# display.net
KiCad netlist of a schematic drawn in EAGLE
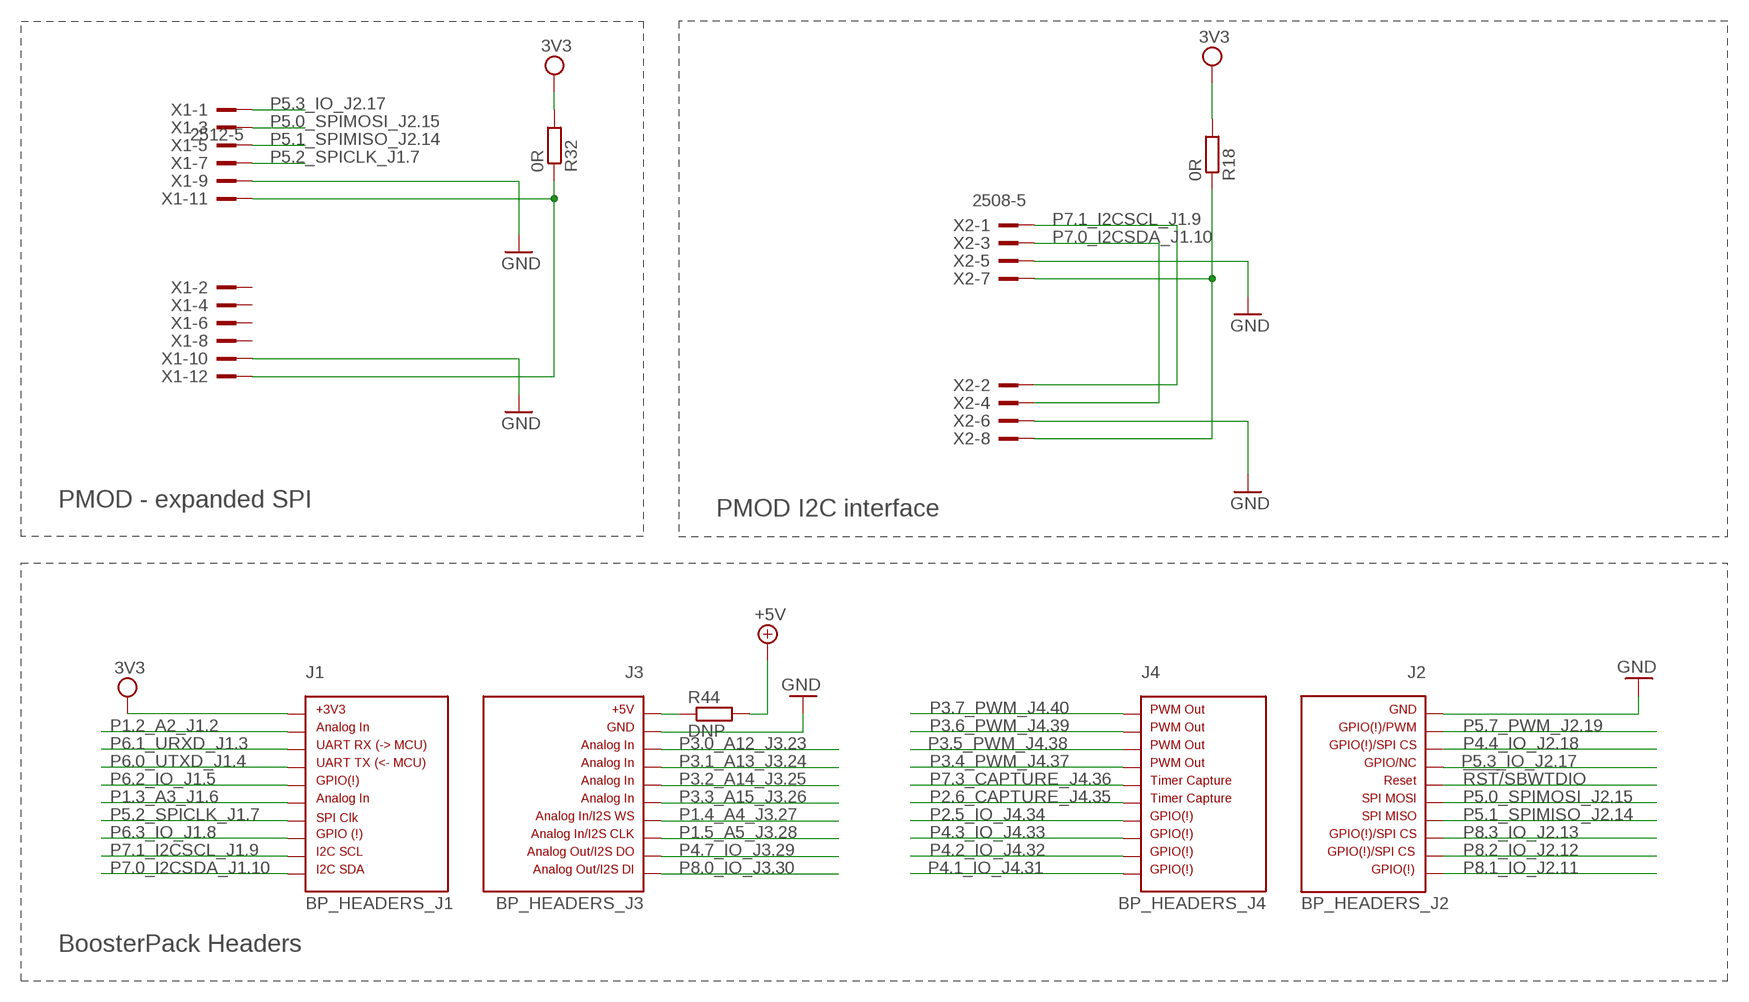
[diagram p0: schematic, sheet 1]
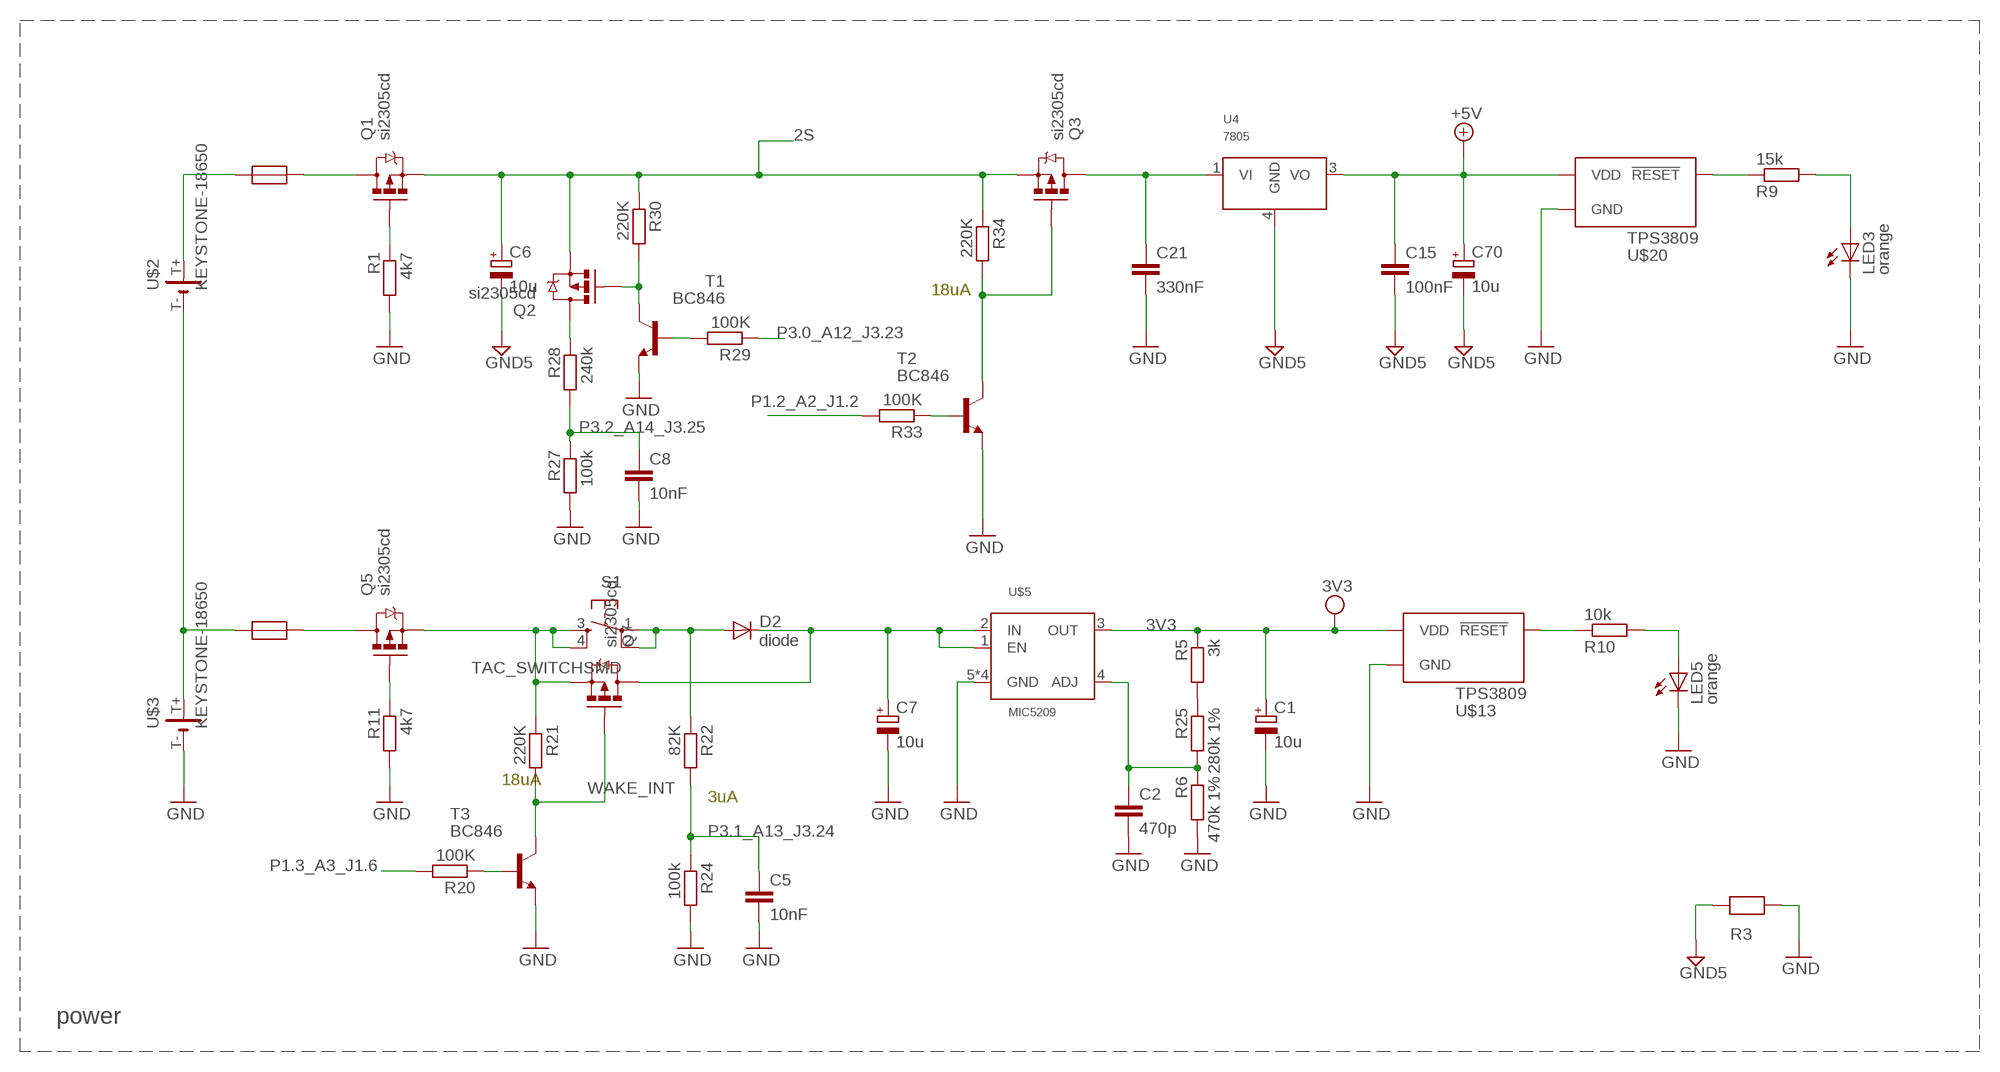
[diagram p1: schematic, sheet 2]
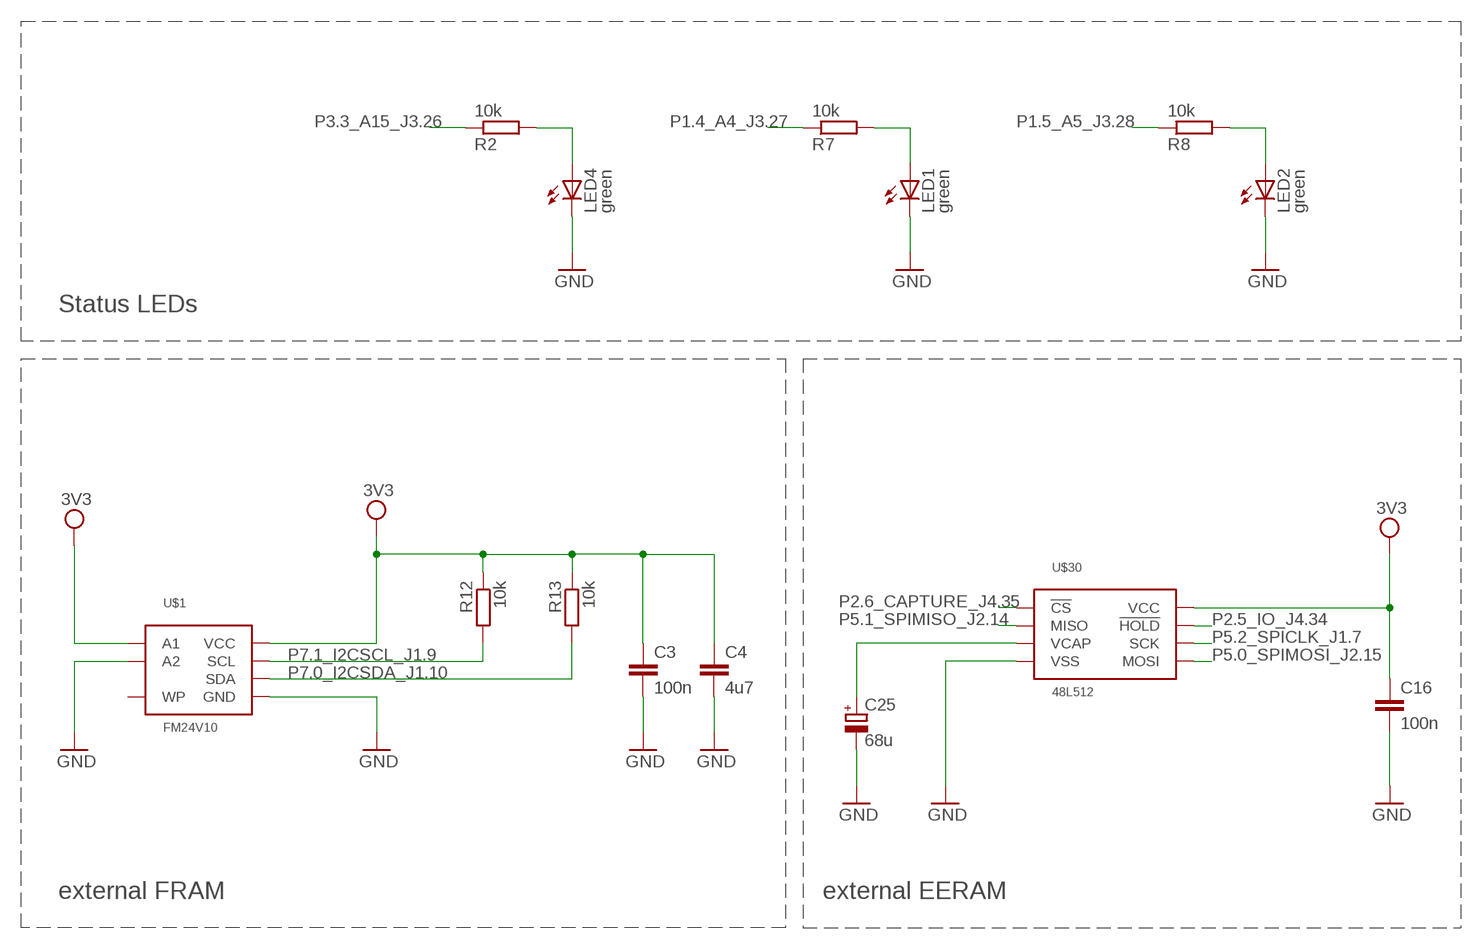
[diagram p2: schematic, sheet 3]
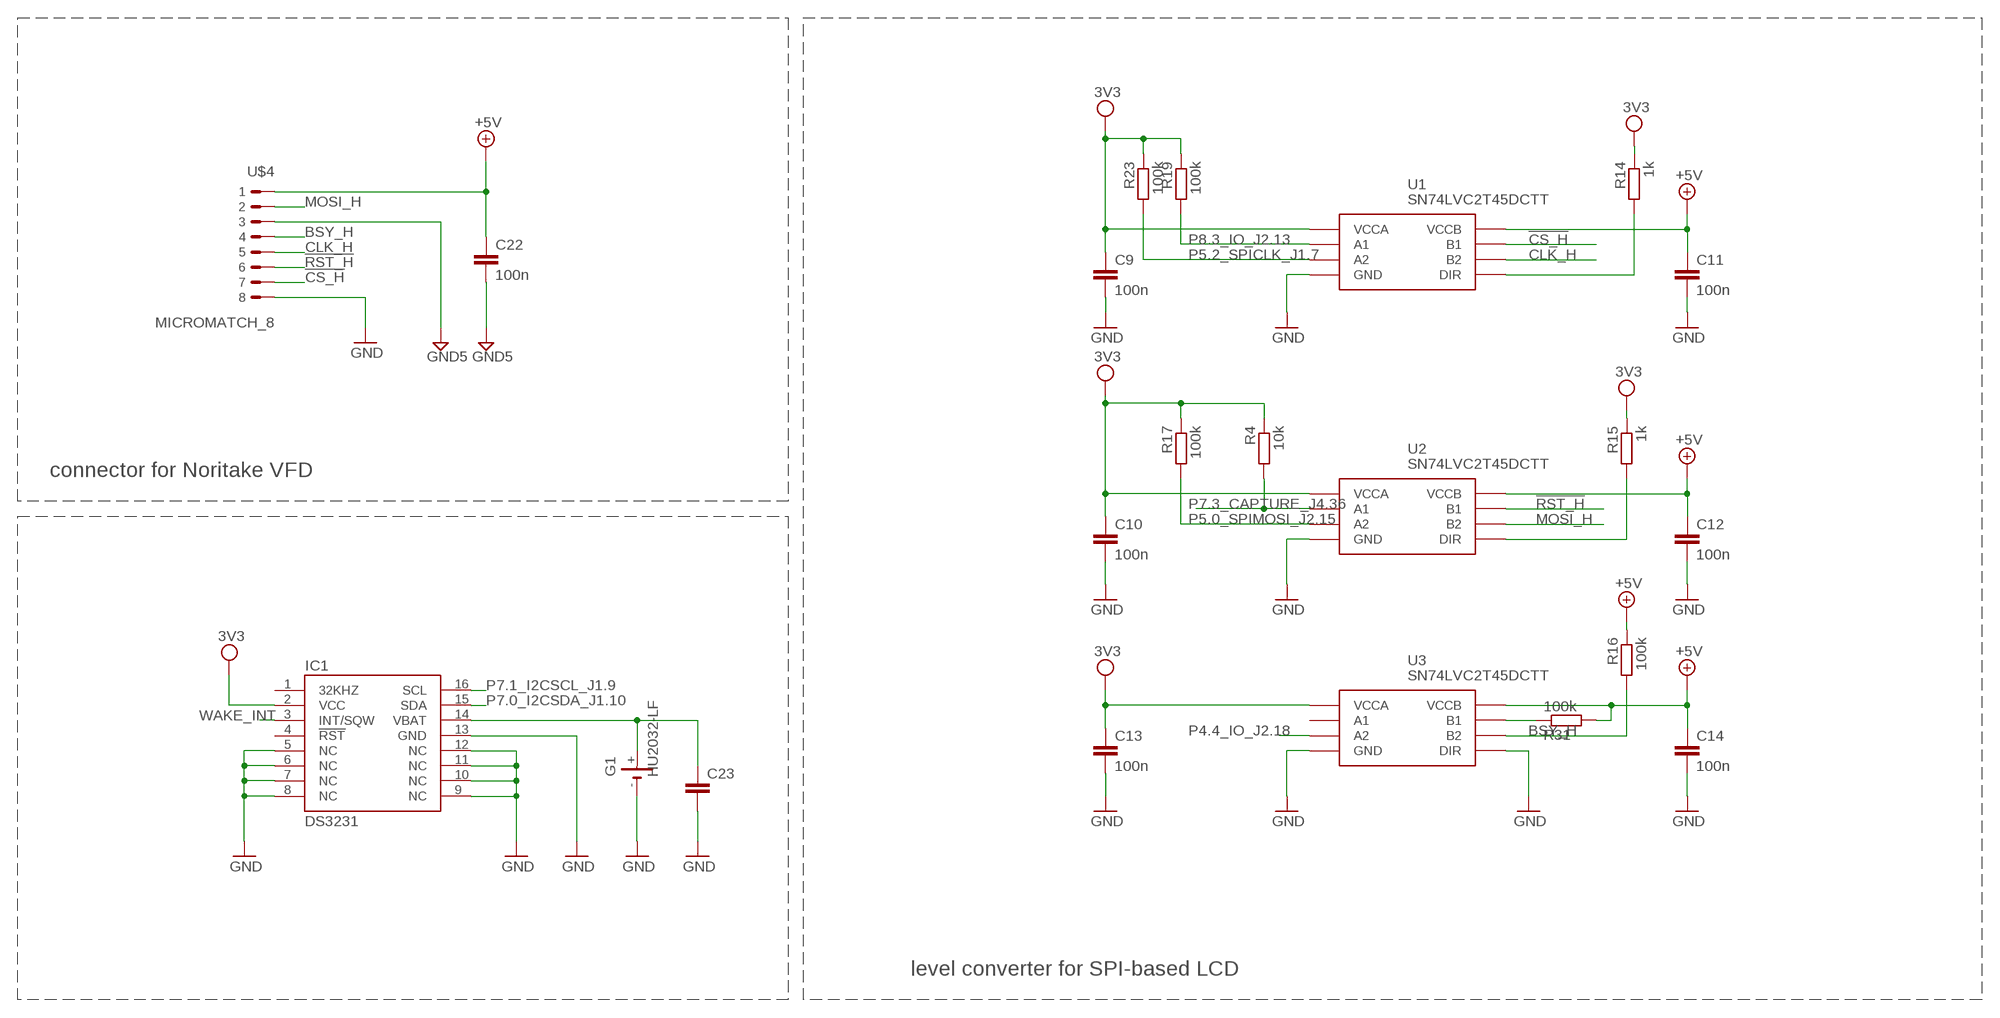
[diagram p3: schematic, sheet 4]
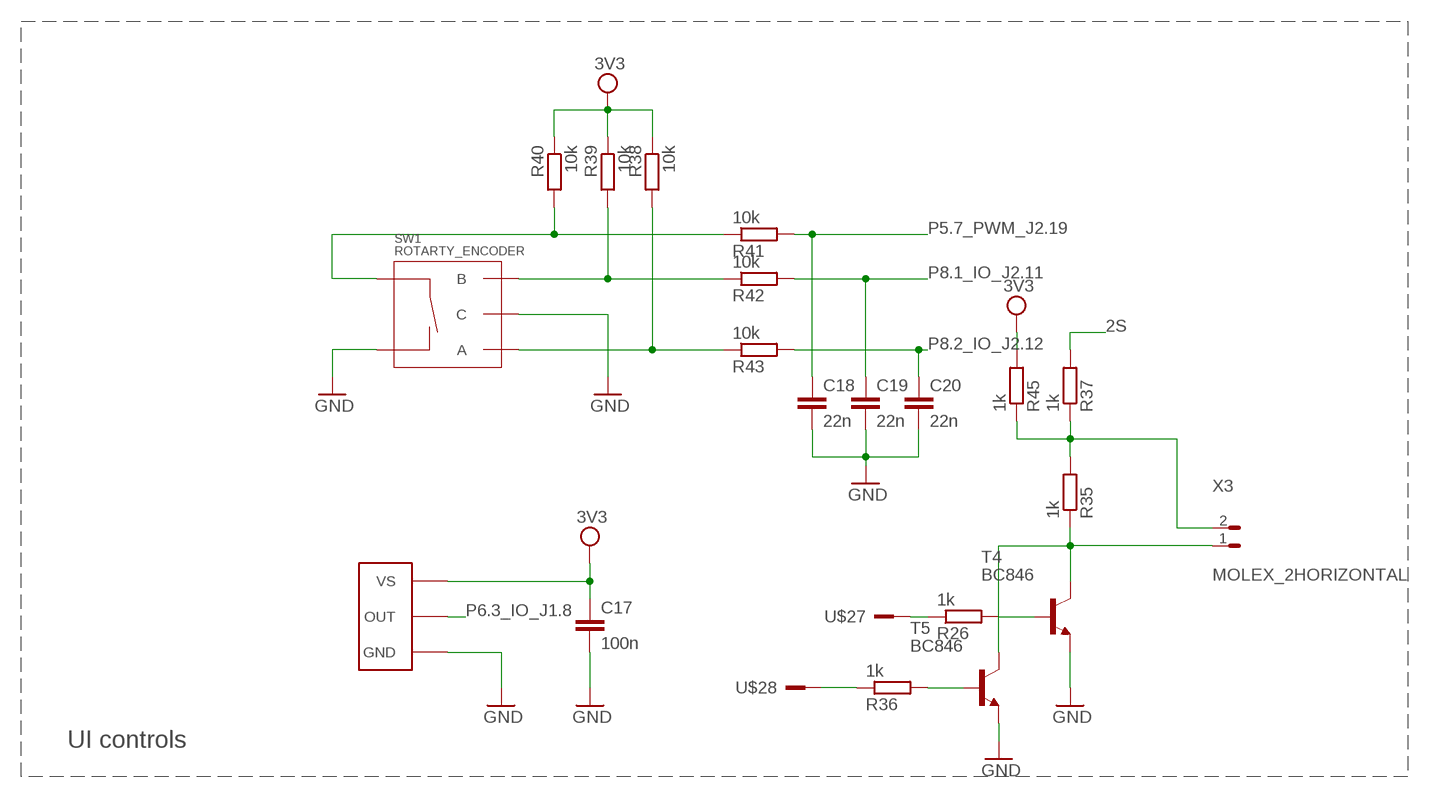
[diagram p4: schematic, sheet 5]

(export (version "E")
  (design (tool "Eeschema 10.0.6"))
  (components
    (comp (ref "C9")
      (value "100n")
      (footprint "eagle-import:C0805")
      (libsource (lib "eagle-import") (part "C-EUC0805"))
    )
    (comp (ref "C10")
      (value "100n")
      (footprint "eagle-import:C0805")
      (libsource (lib "eagle-import") (part "C-EUC0805"))
    )
    (comp (ref "C11")
      (value "100n")
      (footprint "eagle-import:C0805")
      (libsource (lib "eagle-import") (part "C-EUC0805"))
    )
    (comp (ref "C12")
      (value "100n")
      (footprint "eagle-import:C0805")
      (libsource (lib "eagle-import") (part "C-EUC0805"))
    )
    (comp (ref "C13")
      (value "100n")
      (footprint "eagle-import:C0805")
      (libsource (lib "eagle-import") (part "C-EUC0805"))
    )
    (comp (ref "C14")
      (value "100n")
      (footprint "eagle-import:C0805")
      (libsource (lib "eagle-import") (part "C-EUC0805"))
    )
    (comp (ref "C22")
      (value "100n")
      (footprint "eagle-import:C0805")
      (libsource (lib "eagle-import") (part "C-EUC0805"))
    )
    (comp (ref "C23")
      (value "C-EU102-054X133")
      (footprint "eagle-import:C102-054X133")
      (libsource (lib "eagle-import") (part "C-EU102-054X133"))
    )
    (comp (ref "G1")
      (value "HU2032-LF")
      (footprint "eagle-import:HU2032-LF")
      (libsource (lib "eagle-import") (part "HU2032-LF"))
    )
    (comp (ref "IC1")
      (value "DS3231")
      (footprint "eagle-import:SO-16")
      (libsource (lib "eagle-import") (part "DS3231"))
    )
    (comp (ref "R4")
      (value "10k")
      (footprint "eagle-import:R0805W")
      (libsource (lib "eagle-import") (part "R-EU_R0805W"))
    )
    (comp (ref "R14")
      (value "1k")
      (footprint "eagle-import:R0805W")
      (libsource (lib "eagle-import") (part "R-EU_R0805W"))
    )
    (comp (ref "R15")
      (value "1k")
      (footprint "eagle-import:R0805W")
      (libsource (lib "eagle-import") (part "R-EU_R0805W"))
    )
    (comp (ref "R16")
      (value "100k")
      (footprint "eagle-import:R0805W")
      (libsource (lib "eagle-import") (part "R-EU_R0805W"))
    )
    (comp (ref "R17")
      (value "100k")
      (footprint "eagle-import:R0805W")
      (libsource (lib "eagle-import") (part "R-EU_R0805W"))
    )
    (comp (ref "R19")
      (value "100k")
      (footprint "eagle-import:R0805W")
      (libsource (lib "eagle-import") (part "R-EU_R0805W"))
    )
    (comp (ref "R23")
      (value "100k")
      (footprint "eagle-import:R0805W")
      (libsource (lib "eagle-import") (part "R-EU_R0805W"))
    )
    (comp (ref "R31")
      (value "100k")
      (footprint "eagle-import:R0805W")
      (libsource (lib "eagle-import") (part "R-EU_R0805W"))
    )
    (comp (ref "U$4")
      (value "MICROMATCH_8")
      (footprint "eagle-import:MICROMATCH8")
      (libsource (lib "eagle-import") (part "MICROMATCH_8"))
    )
    (comp (ref "U1")
      (value "SN74LVC2T45DCTT")
      (footprint "eagle-import:SSOP8")
      (libsource (lib "eagle-import") (part "SN74LVC2T45DCTT"))
    )
    (comp (ref "U2")
      (value "SN74LVC2T45DCTT")
      (footprint "eagle-import:SSOP8")
      (libsource (lib "eagle-import") (part "SN74LVC2T45DCTT"))
    )
    (comp (ref "U3")
      (value "SN74LVC2T45DCTT")
      (footprint "eagle-import:SSOP8")
      (libsource (lib "eagle-import") (part "SN74LVC2T45DCTT"))
    )
    (comp (ref "C1")
      (value "10u")
      (footprint "eagle-import:153CLV-0405")
      (libsource (lib "eagle-import") (part "CPOL-EU153CLV-0405"))
    )
    (comp (ref "C2")
      (value "470p")
      (footprint "eagle-import:C0805")
      (libsource (lib "eagle-import") (part "C-EUC0805"))
    )
    (comp (ref "C5")
      (value "10nF")
      (footprint "eagle-import:C0805")
      (libsource (lib "eagle-import") (part "C-EUC0805"))
    )
    (comp (ref "C6")
      (value "10u")
      (footprint "eagle-import:153CLV-0405")
      (libsource (lib "eagle-import") (part "CPOL-EU153CLV-0405"))
    )
    (comp (ref "C7")
      (value "10u")
      (footprint "eagle-import:153CLV-0405")
      (libsource (lib "eagle-import") (part "CPOL-EU153CLV-0405"))
    )
    (comp (ref "C8")
      (value "10nF")
      (footprint "eagle-import:C0805")
      (libsource (lib "eagle-import") (part "C-EUC0805"))
    )
    (comp (ref "C15")
      (value "100nF")
      (footprint "eagle-import:C0805")
      (libsource (lib "eagle-import") (part "C-EUC0805"))
    )
    (comp (ref "C21")
      (value "330nF")
      (footprint "eagle-import:C0805")
      (libsource (lib "eagle-import") (part "C-EUC0805"))
    )
    (comp (ref "C70")
      (value "10u")
      (footprint "eagle-import:153CLV-0405")
      (libsource (lib "eagle-import") (part "CPOL-EU153CLV-0405"))
    )
    (comp (ref "D2")
      (value "diode")
      (footprint "eagle-import:SMA-DIODE")
      (libsource (lib "eagle-import") (part "DIODESMA"))
    )
    (comp (ref "LED3")
      (value "orange")
      (footprint "eagle-import:CHIPLED_0805")
      (libsource (lib "eagle-import") (part "LEDCHIPLED_0805"))
    )
    (comp (ref "LED5")
      (value "orange")
      (footprint "eagle-import:CHIPLED_0805")
      (libsource (lib "eagle-import") (part "LEDCHIPLED_0805"))
    )
    (comp (ref "Q1")
      (value "si2305cd")
      (footprint "eagle-import:SOT23-3_POWER")
      (libsource (lib "eagle-import") (part "MOSFET-PCHANNELSMD_POWER"))
    )
    (comp (ref "Q2")
      (value "si2305cd")
      (footprint "eagle-import:SOT23-3_POWER")
      (libsource (lib "eagle-import") (part "MOSFET-PCHANNELSMD_POWER"))
    )
    (comp (ref "Q3")
      (value "si2305cd")
      (footprint "eagle-import:SOT23-3_POWER")
      (libsource (lib "eagle-import") (part "MOSFET-PCHANNELSMD_POWER"))
    )
    (comp (ref "Q5")
      (value "si2305cd")
      (footprint "eagle-import:SOT23-3_POWER")
      (libsource (lib "eagle-import") (part "MOSFET-PCHANNELSMD_POWER"))
    )
    (comp (ref "Q7")
      (value "si2305cd")
      (footprint "eagle-import:SOT23-3_POWER")
      (libsource (lib "eagle-import") (part "MOSFET-PCHANNELSMD_POWER"))
    )
    (comp (ref "R1")
      (value "4k7")
      (footprint "eagle-import:R0805W")
      (libsource (lib "eagle-import") (part "R-EU_R0805W"))
    )
    (comp (ref "R3")
      (value "0R_0805")
      (footprint "eagle-import:R0805W")
      (libsource (lib "eagle-import") (part "0R_0805"))
    )
    (comp (ref "R5")
      (value "3k")
      (footprint "eagle-import:R0805W")
      (libsource (lib "eagle-import") (part "R-EU_R0805W"))
    )
    (comp (ref "R6")
      (value "470k 1%")
      (footprint "eagle-import:R0805W")
      (libsource (lib "eagle-import") (part "R-EU_R0805W"))
    )
    (comp (ref "R9")
      (value "15k")
      (footprint "eagle-import:R0805W")
      (libsource (lib "eagle-import") (part "R-EU_R0805W"))
    )
    (comp (ref "R10")
      (value "10k")
      (footprint "eagle-import:R0805W")
      (libsource (lib "eagle-import") (part "R-EU_R0805W"))
    )
    (comp (ref "R11")
      (value "4k7")
      (footprint "eagle-import:R0805W")
      (libsource (lib "eagle-import") (part "R-EU_R0805W"))
    )
    (comp (ref "R20")
      (value "100K")
      (footprint "eagle-import:R0805W")
      (libsource (lib "eagle-import") (part "R-EU_R0805W"))
    )
    (comp (ref "R21")
      (value "220K")
      (footprint "eagle-import:R0805W")
      (libsource (lib "eagle-import") (part "R-EU_R0805W"))
    )
    (comp (ref "R22")
      (value "82K")
      (footprint "eagle-import:R0805W")
      (libsource (lib "eagle-import") (part "R-EU_R0805W"))
    )
    (comp (ref "R24")
      (value "100k")
      (footprint "eagle-import:R0805W")
      (libsource (lib "eagle-import") (part "R-EU_R0805W"))
    )
    (comp (ref "R25")
      (value "280k 1%")
      (footprint "eagle-import:R0805W")
      (libsource (lib "eagle-import") (part "R-EU_R0805W"))
    )
    (comp (ref "R27")
      (value "100k")
      (footprint "eagle-import:R0805W")
      (libsource (lib "eagle-import") (part "R-EU_R0805W"))
    )
    (comp (ref "R28")
      (value "240k")
      (footprint "eagle-import:R0805W")
      (libsource (lib "eagle-import") (part "R-EU_R0805W"))
    )
    (comp (ref "R29")
      (value "100K")
      (footprint "eagle-import:R0805W")
      (libsource (lib "eagle-import") (part "R-EU_R0805W"))
    )
    (comp (ref "R30")
      (value "220K")
      (footprint "eagle-import:R0805W")
      (libsource (lib "eagle-import") (part "R-EU_R0805W"))
    )
    (comp (ref "R33")
      (value "100K")
      (footprint "eagle-import:R0805W")
      (libsource (lib "eagle-import") (part "R-EU_R0805W"))
    )
    (comp (ref "R34")
      (value "220K")
      (footprint "eagle-import:R0805W")
      (libsource (lib "eagle-import") (part "R-EU_R0805W"))
    )
    (comp (ref "S1")
      (value "TAC_SWITCHSMD")
      (footprint "eagle-import:TACTILE-SWITCH-SMD")
      (libsource (lib "eagle-import") (part "TAC_SWITCHSMD"))
    )
    (comp (ref "T1")
      (value "BC846")
      (footprint "eagle-import:SOT23")
      (libsource (lib "eagle-import") (part "BC846"))
    )
    (comp (ref "T2")
      (value "BC846")
      (footprint "eagle-import:SOT23")
      (libsource (lib "eagle-import") (part "BC846"))
    )
    (comp (ref "T3")
      (value "BC846")
      (footprint "eagle-import:SOT23")
      (libsource (lib "eagle-import") (part "BC846"))
    )
    (comp (ref "U$2")
      (value "KEYSTONE-18650")
      (footprint "eagle-import:KEYSTONE_COMBO_18650")
      (libsource (lib "eagle-import") (part "KEYSTONE-18650"))
    )
    (comp (ref "U$3")
      (value "KEYSTONE-18650")
      (footprint "eagle-import:KEYSTONE_COMBO_18650")
      (libsource (lib "eagle-import") (part "KEYSTONE-18650"))
    )
    (comp (ref "U$5")
      (value "MIC5209")
      (footprint "eagle-import:SO-08")
      (libsource (lib "eagle-import") (part "MIC5209"))
    )
    (comp (ref "U$7")
      (value "Fuse 1A")
      (footprint "eagle-import:0805W")
      (libsource (lib "eagle-import") (part "RESETTABLE_0805"))
    )
    (comp (ref "U$8")
      (value "Fuse 1A")
      (footprint "eagle-import:0805W")
      (libsource (lib "eagle-import") (part "RESETTABLE_0805"))
    )
    (comp (ref "U$13")
      (value "TPS3809")
      (footprint "eagle-import:R_PDSO_G3")
      (libsource (lib "eagle-import") (part "TPS3809"))
    )
    (comp (ref "U$20")
      (value "TPS3809")
      (footprint "eagle-import:R_PDSO_G3")
      (libsource (lib "eagle-import") (part "TPS3809"))
    )
    (comp (ref "U4")
      (value "7805")
      (footprint "eagle-import:D2PACK")
      (libsource (lib "eagle-import") (part "78XX"))
    )
    (comp (ref "C17")
      (value "100n")
      (footprint "eagle-import:C0805")
      (libsource (lib "eagle-import") (part "C-EUC0805"))
    )
    (comp (ref "C18")
      (value "22n")
      (footprint "eagle-import:C0805")
      (libsource (lib "eagle-import") (part "C-EUC0805"))
    )
    (comp (ref "C19")
      (value "22n")
      (footprint "eagle-import:C0805")
      (libsource (lib "eagle-import") (part "C-EUC0805"))
    )
    (comp (ref "C20")
      (value "22n")
      (footprint "eagle-import:C0805")
      (libsource (lib "eagle-import") (part "C-EUC0805"))
    )
    (comp (ref "R26")
      (value "1k")
      (footprint "eagle-import:R0805W")
      (libsource (lib "eagle-import") (part "R-EU_R0805W"))
    )
    (comp (ref "R35")
      (value "1k")
      (footprint "eagle-import:R0805W")
      (libsource (lib "eagle-import") (part "R-EU_R0805W"))
    )
    (comp (ref "R36")
      (value "1k")
      (footprint "eagle-import:R0805W")
      (libsource (lib "eagle-import") (part "R-EU_R0805W"))
    )
    (comp (ref "R37")
      (value "1k")
      (footprint "eagle-import:R0805W")
      (libsource (lib "eagle-import") (part "R-EU_R0805W"))
    )
    (comp (ref "R38")
      (value "10k")
      (footprint "eagle-import:R0805W")
      (libsource (lib "eagle-import") (part "R-EU_R0805W"))
    )
    (comp (ref "R39")
      (value "10k")
      (footprint "eagle-import:R0805W")
      (libsource (lib "eagle-import") (part "R-EU_R0805W"))
    )
    (comp (ref "R40")
      (value "10k")
      (footprint "eagle-import:R0805W")
      (libsource (lib "eagle-import") (part "R-EU_R0805W"))
    )
    (comp (ref "R41")
      (value "10k")
      (footprint "eagle-import:R0805W")
      (libsource (lib "eagle-import") (part "R-EU_R0805W"))
    )
    (comp (ref "R42")
      (value "10k")
      (footprint "eagle-import:R0805W")
      (libsource (lib "eagle-import") (part "R-EU_R0805W"))
    )
    (comp (ref "R43")
      (value "10k")
      (footprint "eagle-import:R0805W")
      (libsource (lib "eagle-import") (part "R-EU_R0805W"))
    )
    (comp (ref "R45")
      (value "1k")
      (footprint "eagle-import:R0805W")
      (libsource (lib "eagle-import") (part "R-EU_R0805W"))
    )
    (comp (ref "SW1")
      (value "ROTARTY_ENCODER")
      (footprint "eagle-import:ROTARY_ENC_PLAIN")
      (libsource (lib "eagle-import") (part "ROTARTY_ENCODER"))
    )
    (comp (ref "T4")
      (value "BC846")
      (footprint "eagle-import:SOT23")
      (libsource (lib "eagle-import") (part "BC846"))
    )
    (comp (ref "T5")
      (value "BC846")
      (footprint "eagle-import:SOT23")
      (libsource (lib "eagle-import") (part "BC846"))
    )
    (comp (ref "U$26")
      (value "TSOP36X")
      (footprint "eagle-import:TSOP36X_SMD")
      (libsource (lib "eagle-import") (part "TSOP36X"))
    )
    (comp (ref "U$27")
      (value "TP")
      (footprint "eagle-import:TP_THT")
      (libsource (lib "eagle-import") (part "TP"))
    )
    (comp (ref "U$28")
      (value "TP")
      (footprint "eagle-import:TP_THT")
      (libsource (lib "eagle-import") (part "TP"))
    )
    (comp (ref "X3")
      (value "MOLEX_2HORIZONTAL")
      (footprint "eagle-import:0530480210")
      (libsource (lib "eagle-import") (part "MOLEX_2HORIZONTAL"))
    )
    (comp (ref "J1")
      (value "BP_HEADERS_J1")
      (footprint "eagle-import:J1")
      (libsource (lib "eagle-import") (part "BP_HEADERS_J1"))
    )
    (comp (ref "J2")
      (value "BP_HEADERS_J2")
      (footprint "eagle-import:J2")
      (libsource (lib "eagle-import") (part "BP_HEADERS_J2"))
    )
    (comp (ref "J3")
      (value "BP_HEADERS_J3")
      (footprint "eagle-import:J3")
      (libsource (lib "eagle-import") (part "BP_HEADERS_J3"))
    )
    (comp (ref "J4")
      (value "BP_HEADERS_J4")
      (footprint "eagle-import:J4")
      (libsource (lib "eagle-import") (part "BP_HEADERS_J4"))
    )
    (comp (ref "R18")
      (value "0R")
      (footprint "eagle-import:0204V")
      (libsource (lib "eagle-import") (part "R-EU_0204/2V"))
    )
    (comp (ref "R32")
      (value "0R")
      (footprint "eagle-import:0204V")
      (libsource (lib "eagle-import") (part "R-EU_0204/2V"))
    )
    (comp (ref "R44")
      (value "DNP")
      (footprint "eagle-import:R0805W")
      (libsource (lib "eagle-import") (part "R-EU_R0805W"))
    )
    (comp (ref "X1")
      (value "2512-5")
      (footprint "eagle-import:PAK100_2500-5-12")
      (fields (field (name "MPN") "N2514-5002RB"))
      (libsource (lib "eagle-import") (part "2512-5"))
    )
    (comp (ref "X2")
      (value "2508-5")
      (footprint "eagle-import:PAK100_2500-5-08")
      (libsource (lib "eagle-import") (part "2508-5"))
    )
    (comp (ref "C3")
      (value "100n")
      (footprint "eagle-import:C0805")
      (libsource (lib "eagle-import") (part "C-EUC0805"))
    )
    (comp (ref "C4")
      (value "4u7")
      (footprint "eagle-import:C0805")
      (libsource (lib "eagle-import") (part "C-EUC0805"))
    )
    (comp (ref "C16")
      (value "100n")
      (footprint "eagle-import:C0805")
      (libsource (lib "eagle-import") (part "C-EUC0805"))
    )
    (comp (ref "C25")
      (value "68u")
      (footprint "eagle-import:SANYO-OSCON_SMD_C6")
      (libsource (lib "eagle-import") (part "CPOL-EUSANYO_SMD_C6"))
    )
    (comp (ref "LED1")
      (value "green")
      (footprint "eagle-import:CHIPLED_0805")
      (libsource (lib "eagle-import") (part "LEDCHIPLED_0805"))
    )
    (comp (ref "LED2")
      (value "green")
      (footprint "eagle-import:CHIPLED_0805")
      (libsource (lib "eagle-import") (part "LEDCHIPLED_0805"))
    )
    (comp (ref "LED4")
      (value "green")
      (footprint "eagle-import:CHIPLED_0805")
      (libsource (lib "eagle-import") (part "LEDCHIPLED_0805"))
    )
    (comp (ref "R2")
      (value "10k")
      (footprint "eagle-import:R0805W")
      (libsource (lib "eagle-import") (part "R-EU_R0805W"))
    )
    (comp (ref "R7")
      (value "10k")
      (footprint "eagle-import:R0805W")
      (libsource (lib "eagle-import") (part "R-EU_R0805W"))
    )
    (comp (ref "R8")
      (value "10k")
      (footprint "eagle-import:R0805W")
      (libsource (lib "eagle-import") (part "R-EU_R0805W"))
    )
    (comp (ref "R12")
      (value "10k")
      (footprint "eagle-import:R0805W")
      (libsource (lib "eagle-import") (part "R-EU_R0805W"))
    )
    (comp (ref "R13")
      (value "10k")
      (footprint "eagle-import:R0805W")
      (libsource (lib "eagle-import") (part "R-EU_R0805W"))
    )
    (comp (ref "U$1")
      (value "FM24V10")
      (footprint "eagle-import:SO-08")
      (libsource (lib "eagle-import") (part "FM24V"))
    )
    (comp (ref "U$30")
      (value "48L512")
      (footprint "eagle-import:SO-08")
      (libsource (lib "eagle-import") (part "48LXXX"))
    )
  )
  (nets
    (net (code "1") (name "+5V") (class "Default")
      (node (ref "C11") (pin "1") (pinfunction "1_1") (pintype "passive"))
      (node (ref "C12") (pin "1") (pinfunction "1_1") (pintype "passive"))
      (node (ref "C14") (pin "1") (pinfunction "1_1") (pintype "passive"))
      (node (ref "C15") (pin "1") (pinfunction "1_1") (pintype "passive"))
      (node (ref "C22") (pin "1") (pinfunction "1_1") (pintype "passive"))
      (node (ref "C70") (pin "+") (pinfunction "+_+") (pintype "passive"))
      (node (ref "R16") (pin "1") (pinfunction "1_1") (pintype "passive"))
      (node (ref "R31") (pin "2") (pinfunction "2_2") (pintype "passive"))
      (node (ref "R44") (pin "2") (pinfunction "2_2") (pintype "passive"))
      (node (ref "U$20") (pin "P$3") (pinfunction "VDD_P$3") (pintype "bidirectional"))
      (node (ref "U$4") (pin "P$1") (pinfunction "1_P$1") (pintype "passive"))
      (node (ref "U1") (pin "P$8") (pinfunction "VCCB_P$8") (pintype "power_in"))
      (node (ref "U2") (pin "P$8") (pinfunction "VCCB_P$8") (pintype "power_in"))
      (node (ref "U3") (pin "P$8") (pinfunction "VCCB_P$8") (pintype "power_in"))
      (node (ref "U4") (pin "3") (pinfunction "VO_3") (pintype "bidirectional"))
    )
    (net (code "2") (name "2S") (class "Default")
      (node (ref "C6") (pin "+") (pinfunction "+_+") (pintype "passive"))
      (node (ref "Q1") (pin "2") (pinfunction "S_2") (pintype "passive"))
      (node (ref "Q2") (pin "2") (pinfunction "S_2") (pintype "passive"))
      (node (ref "Q3") (pin "2") (pinfunction "S_2") (pintype "passive"))
      (node (ref "R30") (pin "1") (pinfunction "1_1") (pintype "passive"))
      (node (ref "R34") (pin "1") (pinfunction "1_1") (pintype "passive"))
      (node (ref "R37") (pin "2") (pinfunction "2_2") (pintype "passive"))
    )
    (net (code "3") (name "3V3") (class "Default")
      (node (ref "C1") (pin "+") (pinfunction "+_+") (pintype "passive"))
      (node (ref "C10") (pin "1") (pinfunction "1_1") (pintype "passive"))
      (node (ref "C13") (pin "1") (pinfunction "1_1") (pintype "passive"))
      (node (ref "C16") (pin "1") (pinfunction "1_1") (pintype "passive"))
      (node (ref "C17") (pin "1") (pinfunction "1_1") (pintype "passive"))
      (node (ref "C3") (pin "1") (pinfunction "1_1") (pintype "passive"))
      (node (ref "C4") (pin "1") (pinfunction "1_1") (pintype "passive"))
      (node (ref "C9") (pin "1") (pinfunction "1_1") (pintype "passive"))
      (node (ref "IC1") (pin "2") (pinfunction "VCC_2") (pintype "power_in"))
      (node (ref "J1") (pin "1") (pinfunction "1_1") (pintype "bidirectional"))
      (node (ref "R12") (pin "1") (pinfunction "1_1") (pintype "passive"))
      (node (ref "R13") (pin "1") (pinfunction "1_1") (pintype "passive"))
      (node (ref "R14") (pin "1") (pinfunction "1_1") (pintype "passive"))
      (node (ref "R15") (pin "1") (pinfunction "1_1") (pintype "passive"))
      (node (ref "R17") (pin "1") (pinfunction "1_1") (pintype "passive"))
      (node (ref "R18") (pin "2") (pinfunction "2_2") (pintype "passive"))
      (node (ref "R19") (pin "1") (pinfunction "1_1") (pintype "passive"))
      (node (ref "R23") (pin "1") (pinfunction "1_1") (pintype "passive"))
      (node (ref "R32") (pin "2") (pinfunction "2_2") (pintype "passive"))
      (node (ref "R38") (pin "1") (pinfunction "1_1") (pintype "passive"))
      (node (ref "R39") (pin "1") (pinfunction "1_1") (pintype "passive"))
      (node (ref "R4") (pin "1") (pinfunction "1_1") (pintype "passive"))
      (node (ref "R40") (pin "1") (pinfunction "1_1") (pintype "passive"))
      (node (ref "R45") (pin "2") (pinfunction "2_2") (pintype "passive"))
      (node (ref "R5") (pin "1") (pinfunction "1_1") (pintype "passive"))
      (node (ref "U$1") (pin "2") (pinfunction "A1_2") (pintype "bidirectional"))
      (node (ref "U$1") (pin "8") (pinfunction "VCC_8") (pintype "bidirectional"))
      (node (ref "U$13") (pin "P$3") (pinfunction "VDD_P$3") (pintype "bidirectional"))
      (node (ref "U$26") (pin "P$3") (pinfunction "VS_P$3") (pintype "bidirectional"))
      (node (ref "U$30") (pin "8") (pinfunction "VCC_8") (pintype "bidirectional"))
      (node (ref "U$5") (pin "3") (pinfunction "OUT_3") (pintype "bidirectional"))
      (node (ref "U1") (pin "P$1") (pinfunction "VCCA_P$1") (pintype "power_in"))
      (node (ref "U2") (pin "P$1") (pinfunction "VCCA_P$1") (pintype "power_in"))
      (node (ref "U3") (pin "P$1") (pinfunction "VCCA_P$1") (pintype "power_in"))
    )
    (net (code "4") (name "BSY_H") (class "Default")
      (node (ref "R16") (pin "2") (pinfunction "2_2") (pintype "passive"))
      (node (ref "U$4") (pin "P$4") (pinfunction "4_P$4") (pintype "passive"))
      (node (ref "U3") (pin "P$6") (pinfunction "B2_P$6") (pintype "bidirectional"))
    )
    (net (code "5") (name "CLK_H") (class "Default")
      (node (ref "U$4") (pin "P$5") (pinfunction "5_P$5") (pintype "passive"))
      (node (ref "U1") (pin "P$6") (pinfunction "B2_P$6") (pintype "bidirectional"))
    )
    (net (code "6") (name "GND") (class "Default")
      (node (ref "C1") (pin "-") (pinfunction "-_-") (pintype "passive"))
      (node (ref "C10") (pin "2") (pinfunction "2_2") (pintype "passive"))
      (node (ref "C11") (pin "2") (pinfunction "2_2") (pintype "passive"))
      (node (ref "C12") (pin "2") (pinfunction "2_2") (pintype "passive"))
      (node (ref "C13") (pin "2") (pinfunction "2_2") (pintype "passive"))
      (node (ref "C14") (pin "2") (pinfunction "2_2") (pintype "passive"))
      (node (ref "C16") (pin "2") (pinfunction "2_2") (pintype "passive"))
      (node (ref "C17") (pin "2") (pinfunction "2_2") (pintype "passive"))
      (node (ref "C18") (pin "2") (pinfunction "2_2") (pintype "passive"))
      (node (ref "C19") (pin "2") (pinfunction "2_2") (pintype "passive"))
      (node (ref "C2") (pin "2") (pinfunction "2_2") (pintype "passive"))
      (node (ref "C20") (pin "2") (pinfunction "2_2") (pintype "passive"))
      (node (ref "C21") (pin "2") (pinfunction "2_2") (pintype "passive"))
      (node (ref "C23") (pin "2") (pinfunction "2_2") (pintype "passive"))
      (node (ref "C25") (pin "-") (pinfunction "-_-") (pintype "passive"))
      (node (ref "C3") (pin "2") (pinfunction "2_2") (pintype "passive"))
      (node (ref "C4") (pin "2") (pinfunction "2_2") (pintype "passive"))
      (node (ref "C5") (pin "2") (pinfunction "2_2") (pintype "passive"))
      (node (ref "C7") (pin "-") (pinfunction "-_-") (pintype "passive"))
      (node (ref "C8") (pin "2") (pinfunction "2_2") (pintype "passive"))
      (node (ref "C9") (pin "2") (pinfunction "2_2") (pintype "passive"))
      (node (ref "G1") (pin "-") (pinfunction "-_-") (pintype "passive"))
      (node (ref "IC1") (pin "10") (pinfunction "NC_10") (pintype "bidirectional"))
      (node (ref "IC1") (pin "11") (pinfunction "NC_11") (pintype "bidirectional"))
      (node (ref "IC1") (pin "12") (pinfunction "NC_12") (pintype "bidirectional"))
      (node (ref "IC1") (pin "13") (pinfunction "GND_13") (pintype "power_in"))
      (node (ref "IC1") (pin "5") (pinfunction "NC_5") (pintype "bidirectional"))
      (node (ref "IC1") (pin "6") (pinfunction "NC_6") (pintype "bidirectional"))
      (node (ref "IC1") (pin "7") (pinfunction "NC_7") (pintype "bidirectional"))
      (node (ref "IC1") (pin "8") (pinfunction "NC_8") (pintype "bidirectional"))
      (node (ref "IC1") (pin "9") (pinfunction "NC_9") (pintype "bidirectional"))
      (node (ref "J2") (pin "20") (pinfunction "20_20") (pintype "bidirectional"))
      (node (ref "J3") (pin "22") (pinfunction "22_22") (pintype "bidirectional"))
      (node (ref "LED1") (pin "C") (pinfunction "C_C") (pintype "passive"))
      (node (ref "LED2") (pin "C") (pinfunction "C_C") (pintype "passive"))
      (node (ref "LED3") (pin "C") (pinfunction "C_C") (pintype "passive"))
      (node (ref "LED4") (pin "C") (pinfunction "C_C") (pintype "passive"))
      (node (ref "LED5") (pin "C") (pinfunction "C_C") (pintype "passive"))
      (node (ref "R1") (pin "2") (pinfunction "2_2") (pintype "passive"))
      (node (ref "R11") (pin "2") (pinfunction "2_2") (pintype "passive"))
      (node (ref "R24") (pin "2") (pinfunction "2_2") (pintype "passive"))
      (node (ref "R27") (pin "2") (pinfunction "2_2") (pintype "passive"))
      (node (ref "R3") (pin "2") (pinfunction "P$2_2") (pintype "bidirectional"))
      (node (ref "R6") (pin "2") (pinfunction "2_2") (pintype "passive"))
      (node (ref "SW1") (pin "C") (pinfunction "C_C") (pintype "bidirectional"))
      (node (ref "SW1") (pin "SW-") (pinfunction "SW-_SW-") (pintype "bidirectional"))
      (node (ref "T1") (pin "2") (pinfunction "E_2") (pintype "passive"))
      (node (ref "T2") (pin "2") (pinfunction "E_2") (pintype "passive"))
      (node (ref "T3") (pin "2") (pinfunction "E_2") (pintype "passive"))
      (node (ref "T4") (pin "2") (pinfunction "E_2") (pintype "passive"))
      (node (ref "T5") (pin "2") (pinfunction "E_2") (pintype "passive"))
      (node (ref "U$1") (pin "3") (pinfunction "A2_3") (pintype "bidirectional"))
      (node (ref "U$1") (pin "4") (pinfunction "GND_4") (pintype "bidirectional"))
      (node (ref "U$13") (pin "P$1") (pinfunction "GND_P$1") (pintype "bidirectional"))
      (node (ref "U$20") (pin "P$1") (pinfunction "GND_P$1") (pintype "bidirectional"))
      (node (ref "U$26") (pin "P$1") (pinfunction "GND_P$1") (pintype "bidirectional"))
      (node (ref "U$3") (pin "T-") (pinfunction "-_T-") (pintype "passive"))
      (node (ref "U$30") (pin "4") (pinfunction "VSS_4") (pintype "bidirectional"))
      (node (ref "U$4") (pin "P$8") (pinfunction "8_P$8") (pintype "passive"))
      (node (ref "U$5") (pin "5") (pinfunction "GND_5") (pintype "bidirectional"))
      (node (ref "U$5") (pin "6") (pinfunction "GND_6") (pintype "bidirectional"))
      (node (ref "U$5") (pin "7") (pinfunction "GND_7") (pintype "bidirectional"))
      (node (ref "U$5") (pin "8") (pinfunction "GND_8") (pintype "bidirectional"))
      (node (ref "U1") (pin "P$4") (pinfunction "GND_P$4") (pintype "power_in"))
      (node (ref "U2") (pin "P$4") (pinfunction "GND_P$4") (pintype "power_in"))
      (node (ref "U3") (pin "P$4") (pinfunction "GND_P$4") (pintype "power_in"))
      (node (ref "U3") (pin "P$5") (pinfunction "DIR_P$5") (pintype "input"))
      (node (ref "X1") (pin "10") (pinfunction "KL_10") (pintype "passive"))
      (node (ref "X1") (pin "9") (pinfunction "KL_9") (pintype "passive"))
      (node (ref "X2") (pin "5") (pinfunction "KL_5") (pintype "passive"))
      (node (ref "X2") (pin "6") (pinfunction "KL_6") (pintype "passive"))
    )
    (net (code "7") (name "GND5") (class "Default")
      (node (ref "C15") (pin "2") (pinfunction "2_2") (pintype "passive"))
      (node (ref "C22") (pin "2") (pinfunction "2_2") (pintype "passive"))
      (node (ref "C6") (pin "-") (pinfunction "-_-") (pintype "passive"))
      (node (ref "C70") (pin "-") (pinfunction "-_-") (pintype "passive"))
      (node (ref "R3") (pin "1") (pinfunction "P$1_1") (pintype "bidirectional"))
      (node (ref "U$4") (pin "P$3") (pinfunction "3_P$3") (pintype "passive"))
      (node (ref "U4") (pin "4") (pinfunction "GND_4") (pintype "bidirectional"))
    )
    (net (code "8") (name "MOSI_H") (class "Default")
      (node (ref "U$4") (pin "P$2") (pinfunction "2_P$2") (pintype "passive"))
      (node (ref "U2") (pin "P$6") (pinfunction "B2_P$6") (pintype "bidirectional"))
    )
    (net (code "9") (name "Net-(D2-PadA)") (class "Default")
      (node (ref "D2") (pin "A") (pinfunction "A_A") (pintype "passive"))
      (node (ref "R22") (pin "1") (pinfunction "1_1") (pintype "passive"))
      (node (ref "S1") (pin "1") (pinfunction "1_1") (pintype "passive"))
      (node (ref "S1") (pin "2") (pinfunction "2_2") (pintype "passive"))
    )
    (net (code "10") (name "Net-(IC1-VBAT)") (class "Default")
      (node (ref "C23") (pin "1") (pinfunction "1_1") (pintype "passive"))
      (node (ref "G1") (pin "+") (pinfunction "+_+") (pintype "passive"))
      (node (ref "IC1") (pin "14") (pinfunction "VBAT_14") (pintype "bidirectional"))
    )
    (net (code "11") (name "Net-(J3-Pad21)") (class "Default")
      (node (ref "J3") (pin "21") (pinfunction "21_21") (pintype "bidirectional"))
      (node (ref "R44") (pin "1") (pinfunction "1_1") (pintype "passive"))
    )
    (net (code "12") (name "Net-(LED1-PadA)") (class "Default")
      (node (ref "LED1") (pin "A") (pinfunction "A_A") (pintype "passive"))
      (node (ref "R7") (pin "2") (pinfunction "2_2") (pintype "passive"))
    )
    (net (code "13") (name "Net-(LED2-PadA)") (class "Default")
      (node (ref "LED2") (pin "A") (pinfunction "A_A") (pintype "passive"))
      (node (ref "R8") (pin "2") (pinfunction "2_2") (pintype "passive"))
    )
    (net (code "14") (name "Net-(LED3-PadA)") (class "Default")
      (node (ref "LED3") (pin "A") (pinfunction "A_A") (pintype "passive"))
      (node (ref "R9") (pin "2") (pinfunction "2_2") (pintype "passive"))
    )
    (net (code "15") (name "Net-(LED4-PadA)") (class "Default")
      (node (ref "LED4") (pin "A") (pinfunction "A_A") (pintype "passive"))
      (node (ref "R2") (pin "2") (pinfunction "2_2") (pintype "passive"))
    )
    (net (code "16") (name "Net-(LED5-PadA)") (class "Default")
      (node (ref "LED5") (pin "A") (pinfunction "A_A") (pintype "passive"))
      (node (ref "R10") (pin "2") (pinfunction "2_2") (pintype "passive"))
    )
    (net (code "17") (name "Net-(Q1-D)") (class "Default")
      (node (ref "Q1") (pin "3") (pinfunction "D_3") (pintype "passive"))
      (node (ref "U$7") (pin "2") (pinfunction "P$2_2") (pintype "bidirectional"))
    )
    (net (code "18") (name "Net-(Q1-G)") (class "Default")
      (node (ref "Q1") (pin "1") (pinfunction "G_1") (pintype "passive"))
      (node (ref "R1") (pin "1") (pinfunction "1_1") (pintype "passive"))
    )
    (net (code "19") (name "Net-(Q2-D)") (class "Default")
      (node (ref "Q2") (pin "3") (pinfunction "D_3") (pintype "passive"))
      (node (ref "R28") (pin "1") (pinfunction "1_1") (pintype "passive"))
    )
    (net (code "20") (name "Net-(Q2-G)") (class "Default")
      (node (ref "Q2") (pin "1") (pinfunction "G_1") (pintype "passive"))
      (node (ref "R30") (pin "2") (pinfunction "2_2") (pintype "passive"))
      (node (ref "T1") (pin "3") (pinfunction "C_3") (pintype "passive"))
    )
    (net (code "21") (name "Net-(Q3-D)") (class "Default")
      (node (ref "C21") (pin "1") (pinfunction "1_1") (pintype "passive"))
      (node (ref "Q3") (pin "3") (pinfunction "D_3") (pintype "passive"))
      (node (ref "U4") (pin "1") (pinfunction "VI_1") (pintype "bidirectional"))
    )
    (net (code "22") (name "Net-(Q3-G)") (class "Default")
      (node (ref "Q3") (pin "1") (pinfunction "G_1") (pintype "passive"))
      (node (ref "R34") (pin "2") (pinfunction "2_2") (pintype "passive"))
      (node (ref "T2") (pin "3") (pinfunction "C_3") (pintype "passive"))
    )
    (net (code "23") (name "Net-(Q5-D)") (class "Default")
      (node (ref "Q5") (pin "3") (pinfunction "D_3") (pintype "passive"))
      (node (ref "U$8") (pin "2") (pinfunction "P$2_2") (pintype "bidirectional"))
    )
    (net (code "24") (name "Net-(Q5-G)") (class "Default")
      (node (ref "Q5") (pin "1") (pinfunction "G_1") (pintype "passive"))
      (node (ref "R11") (pin "1") (pinfunction "1_1") (pintype "passive"))
    )
    (net (code "25") (name "Net-(Q5-S)") (class "Default")
      (node (ref "Q5") (pin "2") (pinfunction "S_2") (pintype "passive"))
      (node (ref "Q7") (pin "2") (pinfunction "S_2") (pintype "passive"))
      (node (ref "R21") (pin "1") (pinfunction "1_1") (pintype "passive"))
      (node (ref "S1") (pin "3") (pinfunction "3_3") (pintype "passive"))
      (node (ref "S1") (pin "4") (pinfunction "4_4") (pintype "passive"))
    )
    (net (code "26") (name "Net-(Q7-D)") (class "Default")
      (node (ref "C7") (pin "+") (pinfunction "+_+") (pintype "passive"))
      (node (ref "D2") (pin "C") (pinfunction "C_C") (pintype "passive"))
      (node (ref "Q7") (pin "3") (pinfunction "D_3") (pintype "passive"))
      (node (ref "U$5") (pin "1") (pinfunction "EN_1") (pintype "bidirectional"))
      (node (ref "U$5") (pin "2") (pinfunction "IN_2") (pintype "bidirectional"))
    )
    (net (code "27") (name "Net-(R25-Pad1)") (class "Default")
      (node (ref "R25") (pin "1") (pinfunction "1_1") (pintype "passive"))
      (node (ref "R5") (pin "2") (pinfunction "2_2") (pintype "passive"))
    )
    (net (code "28") (name "Net-(R38-Pad2)") (class "Default")
      (node (ref "R38") (pin "2") (pinfunction "2_2") (pintype "passive"))
      (node (ref "R43") (pin "1") (pinfunction "1_1") (pintype "passive"))
      (node (ref "SW1") (pin "A") (pinfunction "A_A") (pintype "bidirectional"))
    )
    (net (code "29") (name "Net-(R39-Pad2)") (class "Default")
      (node (ref "R39") (pin "2") (pinfunction "2_2") (pintype "passive"))
      (node (ref "R42") (pin "1") (pinfunction "1_1") (pintype "passive"))
      (node (ref "SW1") (pin "B") (pinfunction "B_B") (pintype "bidirectional"))
    )
    (net (code "30") (name "Net-(R40-Pad2)") (class "Default")
      (node (ref "R40") (pin "2") (pinfunction "2_2") (pintype "passive"))
      (node (ref "R41") (pin "1") (pinfunction "1_1") (pintype "passive"))
      (node (ref "SW1") (pin "SW+") (pinfunction "SW+_SW+") (pintype "bidirectional"))
    )
    (net (code "31") (name "Net-(T1-B)") (class "Default")
      (node (ref "R29") (pin "2") (pinfunction "2_2") (pintype "passive"))
      (node (ref "T1") (pin "1") (pinfunction "B_1") (pintype "passive"))
    )
    (net (code "32") (name "Net-(T2-B)") (class "Default")
      (node (ref "R33") (pin "1") (pinfunction "1_1") (pintype "passive"))
      (node (ref "T2") (pin "1") (pinfunction "B_1") (pintype "passive"))
    )
    (net (code "33") (name "Net-(T3-B)") (class "Default")
      (node (ref "R20") (pin "1") (pinfunction "1_1") (pintype "passive"))
      (node (ref "T3") (pin "1") (pinfunction "B_1") (pintype "passive"))
    )
    (net (code "34") (name "Net-(T4-B)") (class "Default")
      (node (ref "R26") (pin "2") (pinfunction "2_2") (pintype "passive"))
      (node (ref "T4") (pin "1") (pinfunction "B_1") (pintype "passive"))
    )
    (net (code "35") (name "Net-(T4-C)") (class "Default")
      (node (ref "R35") (pin "1") (pinfunction "1_1") (pintype "passive"))
      (node (ref "T4") (pin "3") (pinfunction "C_3") (pintype "passive"))
      (node (ref "T5") (pin "3") (pinfunction "C_3") (pintype "passive"))
      (node (ref "X3") (pin "1") (pinfunction "2_1") (pintype "passive"))
    )
    (net (code "36") (name "Net-(T5-B)") (class "Default")
      (node (ref "R36") (pin "2") (pinfunction "2_2") (pintype "passive"))
      (node (ref "T5") (pin "1") (pinfunction "B_1") (pintype "passive"))
    )
    (net (code "37") (name "Net-(U$2-+)") (class "Default")
      (node (ref "U$2") (pin "T+") (pinfunction "+_T+") (pintype "passive"))
      (node (ref "U$7") (pin "1") (pinfunction "P$1_1") (pintype "bidirectional"))
    )
    (net (code "38") (name "Net-(U$2--)") (class "Default")
      (node (ref "U$2") (pin "T-") (pinfunction "-_T-") (pintype "passive"))
      (node (ref "U$3") (pin "T+") (pinfunction "+_T+") (pintype "passive"))
      (node (ref "U$8") (pin "1") (pinfunction "P$1_1") (pintype "bidirectional"))
    )
    (net (code "39") (name "Net-(U$5-ADJ)") (class "Default")
      (node (ref "C2") (pin "1") (pinfunction "1_1") (pintype "passive"))
      (node (ref "R25") (pin "2") (pinfunction "2_2") (pintype "passive"))
      (node (ref "R6") (pin "1") (pinfunction "1_1") (pintype "passive"))
      (node (ref "U$5") (pin "4") (pinfunction "ADJ_4") (pintype "bidirectional"))
    )
    (net (code "40") (name "Net-(U$13-~{RESET})") (class "Default")
      (node (ref "R10") (pin "1") (pinfunction "1_1") (pintype "passive"))
      (node (ref "U$13") (pin "P$2") (pinfunction "~{RESET}_P$2") (pintype "bidirectional"))
    )
    (net (code "41") (name "Net-(U$20-~{RESET})") (class "Default")
      (node (ref "R9") (pin "1") (pinfunction "1_1") (pintype "passive"))
      (node (ref "U$20") (pin "P$2") (pinfunction "~{RESET}_P$2") (pintype "bidirectional"))
    )
    (net (code "42") (name "Net-(U$27-KL)") (class "Default")
      (node (ref "R26") (pin "1") (pinfunction "1_1") (pintype "passive"))
      (node (ref "U$27") (pin "1") (pinfunction "KL_1") (pintype "passive"))
    )
    (net (code "43") (name "Net-(U$28-KL)") (class "Default")
      (node (ref "R36") (pin "1") (pinfunction "1_1") (pintype "passive"))
      (node (ref "U$28") (pin "1") (pinfunction "KL_1") (pintype "passive"))
    )
    (net (code "44") (name "Net-(U$30-VCAP)") (class "Default")
      (node (ref "C25") (pin "+") (pinfunction "+_+") (pintype "passive"))
      (node (ref "U$30") (pin "3") (pinfunction "VCAP_3") (pintype "bidirectional"))
    )
    (net (code "45") (name "Net-(U1-DIR)") (class "Default")
      (node (ref "R14") (pin "2") (pinfunction "2_2") (pintype "passive"))
      (node (ref "U1") (pin "P$5") (pinfunction "DIR_P$5") (pintype "input"))
    )
    (net (code "46") (name "Net-(U2-DIR)") (class "Default")
      (node (ref "R15") (pin "2") (pinfunction "2_2") (pintype "passive"))
      (node (ref "U2") (pin "P$5") (pinfunction "DIR_P$5") (pintype "input"))
    )
    (net (code "47") (name "Net-(U3-B1)") (class "Default")
      (node (ref "R31") (pin "1") (pinfunction "1_1") (pintype "passive"))
      (node (ref "U3") (pin "P$7") (pinfunction "B1_P$7") (pintype "bidirectional"))
    )
    (net (code "48") (name "Net-(X1C-KL)") (class "Default")
      (node (ref "R32") (pin "1") (pinfunction "1_1") (pintype "passive"))
      (node (ref "X1") (pin "11") (pinfunction "KL_11") (pintype "passive"))
      (node (ref "X1") (pin "12") (pinfunction "KL_12") (pintype "passive"))
    )
    (net (code "49") (name "Net-(X2G-KL)") (class "Default")
      (node (ref "R18") (pin "1") (pinfunction "1_1") (pintype "passive"))
      (node (ref "X2") (pin "7") (pinfunction "KL_7") (pintype "passive"))
      (node (ref "X2") (pin "8") (pinfunction "KL_8") (pintype "passive"))
    )
    (net (code "50") (name "Net-(X3-1)") (class "Default")
      (node (ref "R35") (pin "2") (pinfunction "2_2") (pintype "passive"))
      (node (ref "R37") (pin "1") (pinfunction "1_1") (pintype "passive"))
      (node (ref "R45") (pin "1") (pinfunction "1_1") (pintype "passive"))
      (node (ref "X3") (pin "2") (pinfunction "1_2") (pintype "passive"))
    )
    (net (code "51") (name "P1.2_A2_J1.2") (class "Default")
      (node (ref "J1") (pin "2") (pinfunction "2_2") (pintype "bidirectional"))
      (node (ref "R33") (pin "2") (pinfunction "2_2") (pintype "passive"))
    )
    (net (code "52") (name "P1.3_A3_J1.6") (class "Default")
      (node (ref "J1") (pin "6") (pinfunction "6_6") (pintype "bidirectional"))
      (node (ref "R20") (pin "2") (pinfunction "2_2") (pintype "passive"))
    )
    (net (code "53") (name "P1.4_A4_J3.27") (class "Default")
      (node (ref "J3") (pin "27") (pinfunction "27_27") (pintype "bidirectional"))
      (node (ref "R7") (pin "1") (pinfunction "1_1") (pintype "passive"))
    )
    (net (code "54") (name "P1.5_A5_J3.28") (class "Default")
      (node (ref "J3") (pin "28") (pinfunction "28_28") (pintype "bidirectional"))
      (node (ref "R8") (pin "1") (pinfunction "1_1") (pintype "passive"))
    )
    (net (code "55") (name "P2.5_IO_J4.34") (class "Default")
      (node (ref "J4") (pin "34") (pinfunction "34_34") (pintype "bidirectional"))
      (node (ref "U$30") (pin "7") (pinfunction "~{HOLD}_7") (pintype "bidirectional"))
    )
    (net (code "56") (name "P2.6_CAPTURE_J4.35") (class "Default")
      (node (ref "J4") (pin "35") (pinfunction "35_35") (pintype "bidirectional"))
      (node (ref "U$30") (pin "1") (pinfunction "~{CS}_1") (pintype "bidirectional"))
    )
    (net (code "57") (name "P3.0_A12_J3.23") (class "Default")
      (node (ref "J3") (pin "23") (pinfunction "23_23") (pintype "bidirectional"))
      (node (ref "R29") (pin "1") (pinfunction "1_1") (pintype "passive"))
    )
    (net (code "58") (name "P3.1_A13_J3.24") (class "Default")
      (node (ref "C5") (pin "1") (pinfunction "1_1") (pintype "passive"))
      (node (ref "J3") (pin "24") (pinfunction "24_24") (pintype "bidirectional"))
      (node (ref "R22") (pin "2") (pinfunction "2_2") (pintype "passive"))
      (node (ref "R24") (pin "1") (pinfunction "1_1") (pintype "passive"))
    )
    (net (code "59") (name "P3.2_A14_J3.25") (class "Default")
      (node (ref "C8") (pin "1") (pinfunction "1_1") (pintype "passive"))
      (node (ref "J3") (pin "25") (pinfunction "25_25") (pintype "bidirectional"))
      (node (ref "R27") (pin "1") (pinfunction "1_1") (pintype "passive"))
      (node (ref "R28") (pin "2") (pinfunction "2_2") (pintype "passive"))
    )
    (net (code "60") (name "P3.3_A15_J3.26") (class "Default")
      (node (ref "J3") (pin "26") (pinfunction "26_26") (pintype "bidirectional"))
      (node (ref "R2") (pin "1") (pinfunction "1_1") (pintype "passive"))
    )
    (net (code "61") (name "P3.4_PWM_J4.37") (class "Default")
      (node (ref "J4") (pin "37") (pinfunction "37_37") (pintype "bidirectional"))
    )
    (net (code "62") (name "P3.5_PWM_J4.38") (class "Default")
      (node (ref "J4") (pin "38") (pinfunction "38_38") (pintype "bidirectional"))
    )
    (net (code "63") (name "P3.6_PWM_J4.39") (class "Default")
      (node (ref "J4") (pin "39") (pinfunction "39_39") (pintype "bidirectional"))
    )
    (net (code "64") (name "P3.7_PWM_J4.40") (class "Default")
      (node (ref "J4") (pin "40") (pinfunction "40_40") (pintype "bidirectional"))
    )
    (net (code "65") (name "P4.1_IO_J4.31") (class "Default")
      (node (ref "J4") (pin "31") (pinfunction "31_31") (pintype "bidirectional"))
    )
    (net (code "66") (name "P4.2_IO_J4.32") (class "Default")
      (node (ref "J4") (pin "32") (pinfunction "32_32") (pintype "bidirectional"))
    )
    (net (code "67") (name "P4.3_IO_J4.33") (class "Default")
      (node (ref "J4") (pin "33") (pinfunction "33_33") (pintype "bidirectional"))
    )
    (net (code "68") (name "P4.4_IO_J2.18") (class "Default")
      (node (ref "J2") (pin "18") (pinfunction "18_18") (pintype "bidirectional"))
      (node (ref "U3") (pin "P$3") (pinfunction "A2_P$3") (pintype "bidirectional"))
    )
    (net (code "69") (name "P4.7_IO_J3.29") (class "Default")
      (node (ref "J3") (pin "29") (pinfunction "29_29") (pintype "bidirectional"))
    )
    (net (code "70") (name "P5.0_SPIMOSI_J2.15") (class "Default")
      (node (ref "J2") (pin "15") (pinfunction "15_15") (pintype "bidirectional"))
      (node (ref "R17") (pin "2") (pinfunction "2_2") (pintype "passive"))
      (node (ref "U$30") (pin "5") (pinfunction "MOSI_5") (pintype "bidirectional"))
      (node (ref "U2") (pin "P$3") (pinfunction "A2_P$3") (pintype "bidirectional"))
      (node (ref "X1") (pin "3") (pinfunction "KL_3") (pintype "passive"))
    )
    (net (code "71") (name "P5.1_SPIMISO_J2.14") (class "Default")
      (node (ref "J2") (pin "14") (pinfunction "14_14") (pintype "bidirectional"))
      (node (ref "U$30") (pin "2") (pinfunction "MISO_2") (pintype "bidirectional"))
      (node (ref "X1") (pin "5") (pinfunction "KL_5") (pintype "passive"))
    )
    (net (code "72") (name "P5.2_SPICLK_J1.7") (class "Default")
      (node (ref "J1") (pin "7") (pinfunction "7_7") (pintype "bidirectional"))
      (node (ref "R23") (pin "2") (pinfunction "2_2") (pintype "passive"))
      (node (ref "U$30") (pin "6") (pinfunction "SCK_6") (pintype "bidirectional"))
      (node (ref "U1") (pin "P$3") (pinfunction "A2_P$3") (pintype "bidirectional"))
      (node (ref "X1") (pin "7") (pinfunction "KL_7") (pintype "passive"))
    )
    (net (code "73") (name "P5.3_IO_J2.17") (class "Default")
      (node (ref "J2") (pin "17") (pinfunction "17_17") (pintype "bidirectional"))
      (node (ref "X1") (pin "1") (pinfunction "KL_1") (pintype "passive"))
    )
    (net (code "74") (name "P5.7_PWM_J2.19") (class "Default")
      (node (ref "C18") (pin "1") (pinfunction "1_1") (pintype "passive"))
      (node (ref "J2") (pin "19") (pinfunction "19_19") (pintype "bidirectional"))
      (node (ref "R41") (pin "2") (pinfunction "2_2") (pintype "passive"))
    )
    (net (code "75") (name "P6.0_UTXD_J1.4") (class "Default")
      (node (ref "J1") (pin "4") (pinfunction "4_4") (pintype "bidirectional"))
    )
    (net (code "76") (name "P6.1_URXD_J1.3") (class "Default")
      (node (ref "J1") (pin "3") (pinfunction "3_3") (pintype "bidirectional"))
    )
    (net (code "77") (name "P6.2_IO_J1.5") (class "Default")
      (node (ref "J1") (pin "5") (pinfunction "5_5") (pintype "bidirectional"))
    )
    (net (code "78") (name "P6.3_IO_J1.8") (class "Default")
      (node (ref "J1") (pin "8") (pinfunction "8_8") (pintype "bidirectional"))
      (node (ref "U$26") (pin "P$4") (pinfunction "OUT_P$4") (pintype "bidirectional"))
    )
    (net (code "79") (name "P7.0_I2CSDA_J1.10") (class "Default")
      (node (ref "IC1") (pin "15") (pinfunction "SDA_15") (pintype "bidirectional"))
      (node (ref "J1") (pin "10") (pinfunction "10_10") (pintype "bidirectional"))
      (node (ref "R13") (pin "2") (pinfunction "2_2") (pintype "passive"))
      (node (ref "U$1") (pin "5") (pinfunction "SDA_5") (pintype "bidirectional"))
      (node (ref "X2") (pin "3") (pinfunction "KL_3") (pintype "passive"))
      (node (ref "X2") (pin "4") (pinfunction "KL_4") (pintype "passive"))
    )
    (net (code "80") (name "P7.1_I2CSCL_J1.9") (class "Default")
      (node (ref "IC1") (pin "16") (pinfunction "SCL_16") (pintype "bidirectional"))
      (node (ref "J1") (pin "9") (pinfunction "9_9") (pintype "bidirectional"))
      (node (ref "R12") (pin "2") (pinfunction "2_2") (pintype "passive"))
      (node (ref "U$1") (pin "6") (pinfunction "SCL_6") (pintype "bidirectional"))
      (node (ref "X2") (pin "1") (pinfunction "KL_1") (pintype "passive"))
      (node (ref "X2") (pin "2") (pinfunction "KL_2") (pintype "passive"))
    )
    (net (code "81") (name "P7.3_CAPTURE_J4.36") (class "Default")
      (node (ref "J4") (pin "36") (pinfunction "36_36") (pintype "bidirectional"))
      (node (ref "R4") (pin "2") (pinfunction "2_2") (pintype "passive"))
      (node (ref "U2") (pin "P$2") (pinfunction "A1_P$2") (pintype "bidirectional"))
    )
    (net (code "82") (name "P8.0_IO_J3.30") (class "Default")
      (node (ref "J3") (pin "30") (pinfunction "30_30") (pintype "bidirectional"))
    )
    (net (code "83") (name "P8.1_IO_J2.11") (class "Default")
      (node (ref "C19") (pin "1") (pinfunction "1_1") (pintype "passive"))
      (node (ref "J2") (pin "11") (pinfunction "11_11") (pintype "bidirectional"))
      (node (ref "R42") (pin "2") (pinfunction "2_2") (pintype "passive"))
    )
    (net (code "84") (name "P8.2_IO_J2.12") (class "Default")
      (node (ref "C20") (pin "1") (pinfunction "1_1") (pintype "passive"))
      (node (ref "J2") (pin "12") (pinfunction "12_12") (pintype "bidirectional"))
      (node (ref "R43") (pin "2") (pinfunction "2_2") (pintype "passive"))
    )
    (net (code "85") (name "P8.3_IO_J2.13") (class "Default")
      (node (ref "J2") (pin "13") (pinfunction "13_13") (pintype "bidirectional"))
      (node (ref "R19") (pin "2") (pinfunction "2_2") (pintype "passive"))
      (node (ref "U1") (pin "P$2") (pinfunction "A1_P$2") (pintype "bidirectional"))
    )
    (net (code "86") (name "WAKE_INT") (class "Default")
      (node (ref "IC1") (pin "3") (pinfunction "INT/SQW_3") (pintype "bidirectional"))
      (node (ref "Q7") (pin "1") (pinfunction "G_1") (pintype "passive"))
      (node (ref "R21") (pin "2") (pinfunction "2_2") (pintype "passive"))
      (node (ref "T3") (pin "3") (pinfunction "C_3") (pintype "passive"))
    )
    (net (code "87") (name "unconnected-(G1-+-Pad+@1)") (class "Default")
      (node (ref "G1") (pin "+@1") (pinfunction "+_+@1") (pintype "passive"))
    )
    (net (code "88") (name "unconnected-(IC1-32KHZ-Pad1)") (class "Default")
      (node (ref "IC1") (pin "1") (pinfunction "32KHZ_1") (pintype "bidirectional"))
    )
    (net (code "89") (name "unconnected-(IC1-~{RST}-Pad4)") (class "Default")
      (node (ref "IC1") (pin "4") (pinfunction "~{RST}_4") (pintype "bidirectional"))
    )
    (net (code "90") (name "unconnected-(U$1-WP-Pad7)") (class "Default")
      (node (ref "U$1") (pin "7") (pinfunction "WP_7") (pintype "bidirectional"))
    )
    (net (code "91") (name "unconnected-(U3-A1-PadP$2)") (class "Default")
      (node (ref "U3") (pin "P$2") (pinfunction "A1_P$2") (pintype "bidirectional"))
    )
    (net (code "92") (name "unconnected-(X1E-KL-Pad2)") (class "Default")
      (node (ref "X1") (pin "2") (pinfunction "KL_2") (pintype "passive"))
    )
    (net (code "93") (name "unconnected-(X1G-KL-Pad4)") (class "Default")
      (node (ref "X1") (pin "4") (pinfunction "KL_4") (pintype "passive"))
    )
    (net (code "94") (name "unconnected-(X1I-KL-Pad6)") (class "Default")
      (node (ref "X1") (pin "6") (pinfunction "KL_6") (pintype "passive"))
    )
    (net (code "95") (name "unconnected-(X1K-KL-Pad8)") (class "Default")
      (node (ref "X1") (pin "8") (pinfunction "KL_8") (pintype "passive"))
    )
    (net (code "96") (name "~{CS_H}") (class "Default")
      (node (ref "U$4") (pin "P$7") (pinfunction "7_P$7") (pintype "passive"))
      (node (ref "U1") (pin "P$7") (pinfunction "B1_P$7") (pintype "bidirectional"))
    )
    (net (code "97") (name "~{RST_H}") (class "Default")
      (node (ref "U$4") (pin "P$6") (pinfunction "6_P$6") (pintype "passive"))
      (node (ref "U2") (pin "P$7") (pinfunction "B1_P$7") (pintype "bidirectional"))
    )
    (net (code "98") (name "~{RST}{slash}SBWTDIO") (class "Default")
      (node (ref "J2") (pin "16") (pinfunction "16_16") (pintype "bidirectional"))
    )
  )
)
